# PSU.net
KiCad netlist of a schematic drawn in Altium Designer
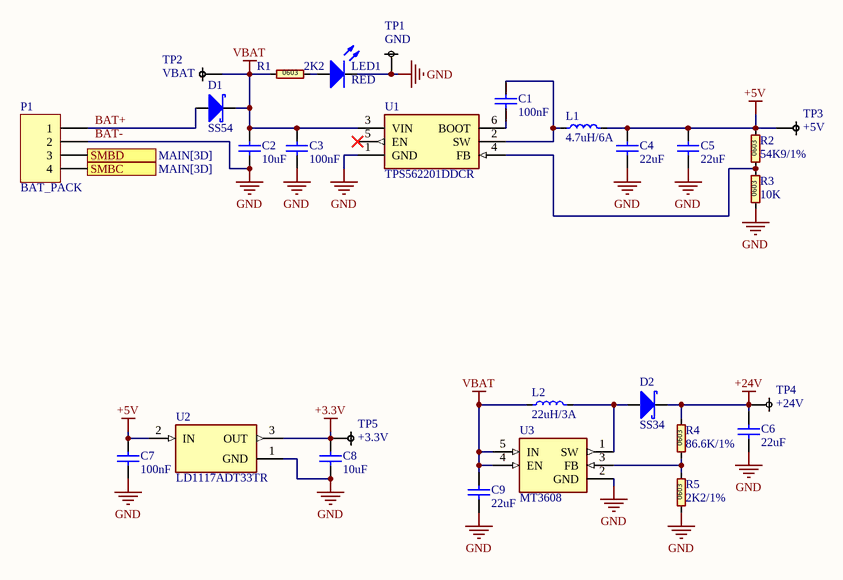
[diagram p0: PSU.SchDoc]

(export (version "E")
  (design (tool "Eeschema 10.0.6"))
  (components
    (comp (ref "C1")
      (value "100nF")
      (footprint "C0603")
      (description "0603 SMD Non-Polarity Capacitor")
      (fields (field (name "MFR.PART #") "CC1206KRX7R9BB104") (field (name "LCSC PART #") "C82601"))
      (libsource (lib "AB_SF") (part "Capacitor 0603 (Inch)"))
    )
    (comp (ref "C2")
      (value "10uF")
      (footprint "C1206")
      (description "1206 SMD Non-Polarity Capacitor")
      (fields (field (name "MFR.PART #") "CC1206KKX5R9BB106") (field (name "LCSC PART #") "C100122"))
      (libsource (lib "AB_SF") (part "Capacitor 1206 (Inch)"))
    )
    (comp (ref "C3")
      (value "100nF")
      (footprint "C0603")
      (description "0603 SMD Non-Polarity Capacitor")
      (libsource (lib "AB_SF") (part "Capacitor 0603 (Inch)"))
    )
    (comp (ref "C4")
      (value "22uF")
      (footprint "C0603")
      (description "0603 SMD Non-Polarity Capacitor")
      (fields (field (name "MFR.PART #") "GRM188R61A226ME15D") (field (name "LCSC PART #") "C84419"))
      (libsource (lib "AB_SF") (part "Capacitor 0603 (Inch)"))
    )
    (comp (ref "C5")
      (value "22uF")
      (footprint "C0603")
      (description "0603 SMD Non-Polarity Capacitor")
      (fields (field (name "MFR.PART #") "GRM188R61A226ME15D") (field (name "LCSC PART #") "C84419"))
      (libsource (lib "AB_SF") (part "Capacitor 0603 (Inch)"))
    )
    (comp (ref "C6")
      (value "22uF")
      (footprint "C1206")
      (description "1206 SMD Non-Polarity Capacitor")
      (fields (field (name "MFR.PART #") "CC1206KKX5R8BB226") (field (name "LCSC PART #") "C2178233"))
      (libsource (lib "AB_SF") (part "Capacitor 1206 (Inch)"))
    )
    (comp (ref "C7")
      (value "100nF")
      (footprint "C0603")
      (description "0603 SMD Non-Polarity Capacitor")
      (libsource (lib "AB_SF") (part "Capacitor 0603 (Inch)"))
    )
    (comp (ref "C8")
      (value "10uF")
      (footprint "C1206")
      (description "1206 SMD Non-Polarity Capacitor")
      (libsource (lib "AB_SF") (part "Capacitor 1206 (Inch)"))
    )
    (comp (ref "C9")
      (value "22uF")
      (footprint "C1206")
      (description "1206 SMD Non-Polarity Capacitor")
      (fields (field (name "MFR.PART #") "CC1206KKX5R8BB226") (field (name "LCSC PART #") "C2178233"))
      (libsource (lib "AB_SF") (part "Capacitor 1206 (Inch)"))
    )
    (comp (ref "D1")
      (value "SS54")
      (footprint "DO-214AC")
      (description "40V Independent 550mV@5A 5A SMA(DO-214AC) Schottky Diodes")
      (fields (field (name "LCSC PART #") "C22452"))
      (libsource (lib "AB_SF") (part "SS54"))
    )
    (comp (ref "D2")
      (value "SS34")
      (footprint "DO-214AC")
      (description "Schottky SS34 DO-214AC")
      (fields (field (name "LCSC PART #") "C3040628"))
      (libsource (lib "AB_SF") (part "SS34"))
    )
    (comp (ref "L1")
      (value "4.7uH/6A")
      (footprint "IND_2926 (7467)")
      (description "Inductor with Package: 2926 (7467)")
      (fields (field (name "MFR.PART #") "FXL0630-4R7-M") (field (name "LCSC PART #") "C167220"))
      (libsource (lib "AB_SF") (part "INDUCTOR 2926"))
    )
    (comp (ref "L2")
      (value "22uH/3A")
      (footprint "IND_2926 (7467)")
      (description "Inductor with Package: 2926 (7467)")
      (fields (field (name "MFR.PART #") "YSPI0630A-220M") (field (name "LCSC PART #") "C497873"))
      (libsource (lib "AB_SF") (part "INDUCTOR 2926"))
    )
    (comp (ref "LED1")
      (value "RED")
      (footprint "LED0603")
      (description "0603 LED")
      (fields (field (name "MFR.PART #") "KT-0603R") (field (name "LCSC PART #") "C2286"))
      (libsource (lib "AB_SF") (part "LED 0603"))
    )
    (comp (ref "P1")
      (value "BAT_PACK")
      (footprint "JST_XH-2.54")
      (description "CONNECTOR HEADER")
      (fields (field (name "PUBLISHER") "Altium Limited"))
      (libsource (lib "AB_SF") (part "Connector 4P"))
    )
    (comp (ref "R1")
      (value "2K2")
      (footprint "R0603")
      (description "0603 SMD Thick Resistor")
      (fields (field (name "MFR.PART #") "RC0603JR-072K2L") (field (name "LCSC PART #") "C113303"))
      (libsource (lib "") (part "Resistor 0603 (Inch)_1"))
    )
    (comp (ref "R2")
      (value "54K9/1%")
      (footprint "R0603")
      (description "0603 SMD Thick Resistor")
      (fields (field (name "MFR.PART #") "RC0603FR-0754K9L") (field (name "LCSC PART #") "C185321"))
      (libsource (lib "AB_SF") (part "Resistor 0603 (Inch)"))
    )
    (comp (ref "R3")
      (value "10K")
      (footprint "R0603")
      (description "0603 SMD Thick Resistor")
      (fields (field (name "MFR.PART #") "RC0603FR-0710KL") (field (name "LCSC PART #") "C98220"))
      (libsource (lib "AB_SF") (part "Resistor 0603 (Inch)"))
    )
    (comp (ref "R4")
      (value "86.6K/1%")
      (footprint "R0603")
      (description "0603 SMD Thick Resistor")
      (fields (field (name "MFR.PART #") "RC0603FR-0786K6L") (field (name "LCSC PART #") "C141683"))
      (libsource (lib "AB_SF") (part "Resistor 0603 (Inch)"))
    )
    (comp (ref "R5")
      (value "2K2/1%")
      (footprint "R0603")
      (description "0603 SMD Thick Resistor")
      (fields (field (name "MFR.PART #") "RC0603JR-072K2L") (field (name "LCSC PART #") "C113303"))
      (libsource (lib "AB_SF") (part "Resistor 0603 (Inch)"))
    )
    (comp (ref "TP1")
      (value "GND")
      (footprint "PAD")
      (description "Thick Pad")
      (libsource (lib "AB_SF") (part "Test Point"))
    )
    (comp (ref "TP2")
      (value "VBAT")
      (footprint "PAD")
      (description "Thick Pad")
      (libsource (lib "AB_SF") (part "Test Point"))
    )
    (comp (ref "TP3")
      (value "+5V")
      (footprint "PAD")
      (description "Thick Pad")
      (libsource (lib "AB_SF") (part "Test Point"))
    )
    (comp (ref "TP4")
      (value "+24V")
      (footprint "PAD_HOLE")
      (description "Thick Pad")
      (libsource (lib "AB_SF") (part "Test Point"))
    )
    (comp (ref "TP5")
      (value "+3.3V")
      (footprint "PAD")
      (description "Thick Pad")
      (libsource (lib "AB_SF") (part "Test Point"))
    )
    (comp (ref "U1")
      (value "TPS562201DDCR")
      (footprint "SOT-23-6")
      (description "4.5 V to 17 V input, 2 A output, synchronous step-down converter in Eco-mode")
      (fields (field (name "LCSC PART #") "C90061"))
      (libsource (lib "AB_SF") (part "TPS562201DDCR"))
    )
    (comp (ref "U2")
      (value "LD1117ADT33TR")
      (footprint "DPAK")
      (description "Linear Voltage Regulator IC Positive Fixed 1 Output 3.3V 1A")
      (fields (field (name "LCSC PART #") "C157401"))
      (libsource (lib "AB_SF") (part "LD1117ADT33TR"))
    )
    (comp (ref "U3")
      (value "MT3608")
      (footprint "SOT-23-6")
      (description "High Efficiency 1.2MHz2A Step Up Converter")
      (fields (field (name "LCSC PART #") "C84817"))
      (libsource (lib "AB_SF") (part "MT3608"))
    )
  )
  (nets
    (net (code "1") (name "+3.3V") (class "Default")
      (node (ref "C8") (pin "2") (pinfunction "2_2") (pintype "passive"))
      (node (ref "TP5") (pin "1") (pinfunction "1_1") (pintype "passive"))
      (node (ref "U2") (pin "3") (pinfunction "OUT_3") (pintype "output"))
    )
    (net (code "2") (name "+5V") (class "Default")
      (node (ref "C4") (pin "2") (pinfunction "2_2") (pintype "passive"))
      (node (ref "C5") (pin "2") (pinfunction "2_2") (pintype "passive"))
      (node (ref "C7") (pin "2") (pinfunction "2_2") (pintype "passive"))
      (node (ref "L1") (pin "2") (pinfunction "2_2") (pintype "passive"))
      (node (ref "R2") (pin "2") (pinfunction "2_2") (pintype "passive"))
      (node (ref "TP3") (pin "1") (pinfunction "1_1") (pintype "passive"))
      (node (ref "U2") (pin "2") (pinfunction "IN_2") (pintype "input"))
    )
    (net (code "3") (name "+24V") (class "Default")
      (node (ref "C6") (pin "2") (pinfunction "2_2") (pintype "passive"))
      (node (ref "D2") (pin "C") (pinfunction "K_C") (pintype "passive"))
      (node (ref "R4") (pin "2") (pinfunction "2_2") (pintype "passive"))
      (node (ref "TP4") (pin "1") (pinfunction "1_1") (pintype "passive"))
    )
    (net (code "4") (name "/BAT+") (class "Default")
      (node (ref "D1") (pin "A") (pinfunction "A_A") (pintype "passive"))
      (node (ref "P1") (pin "1") (pinfunction "1_1") (pintype "passive"))
    )
    (net (code "5") (name "/SMBC") (class "Default")
      (node (ref "P1") (pin "4") (pinfunction "4_4") (pintype "passive"))
    )
    (net (code "6") (name "/SMBD") (class "Default")
      (node (ref "P1") (pin "3") (pinfunction "3_3") (pintype "passive"))
    )
    (net (code "7") (name "GND") (class "Default")
      (node (ref "C2") (pin "1") (pinfunction "1_1") (pintype "passive"))
      (node (ref "C3") (pin "1") (pinfunction "1_1") (pintype "passive"))
      (node (ref "C4") (pin "1") (pinfunction "1_1") (pintype "passive"))
      (node (ref "C5") (pin "1") (pinfunction "1_1") (pintype "passive"))
      (node (ref "C6") (pin "1") (pinfunction "1_1") (pintype "passive"))
      (node (ref "C7") (pin "1") (pinfunction "1_1") (pintype "passive"))
      (node (ref "C8") (pin "1") (pinfunction "1_1") (pintype "passive"))
      (node (ref "C9") (pin "1") (pinfunction "1_1") (pintype "passive"))
      (node (ref "LED1") (pin "2") (pinfunction "K_2") (pintype "passive"))
      (node (ref "P1") (pin "2") (pinfunction "2_2") (pintype "passive"))
      (node (ref "R3") (pin "1") (pinfunction "1_1") (pintype "passive"))
      (node (ref "R5") (pin "1") (pinfunction "1_1") (pintype "passive"))
      (node (ref "TP1") (pin "1") (pinfunction "1_1") (pintype "passive"))
      (node (ref "U1") (pin "1") (pinfunction "GND_1") (pintype "power_in"))
      (node (ref "U2") (pin "1") (pinfunction "GND_1") (pintype "power_in"))
      (node (ref "U3") (pin "2") (pinfunction "GND_2") (pintype "power_in"))
    )
    (net (code "8") (name "Net-(LED1-A)") (class "Default")
      (node (ref "LED1") (pin "1") (pinfunction "A_1") (pintype "passive"))
      (node (ref "R1") (pin "2") (pinfunction "2_2") (pintype "passive"))
    )
    (net (code "9") (name "Net-(U1-BOOT)") (class "Default")
      (node (ref "C1") (pin "1") (pinfunction "1_1") (pintype "passive"))
      (node (ref "U1") (pin "6") (pinfunction "BOOT_6") (pintype "passive"))
    )
    (net (code "10") (name "Net-(U1-FB)") (class "Default")
      (node (ref "R2") (pin "1") (pinfunction "1_1") (pintype "passive"))
      (node (ref "R3") (pin "2") (pinfunction "2_2") (pintype "passive"))
      (node (ref "U1") (pin "4") (pinfunction "FB_4") (pintype "input"))
    )
    (net (code "11") (name "Net-(U1-SW)") (class "Default")
      (node (ref "C1") (pin "2") (pinfunction "2_2") (pintype "passive"))
      (node (ref "L1") (pin "1") (pinfunction "1_1") (pintype "passive"))
      (node (ref "U1") (pin "2") (pinfunction "SW_2") (pintype "passive"))
    )
    (net (code "12") (name "Net-(U3-FB)") (class "Default")
      (node (ref "R4") (pin "1") (pinfunction "1_1") (pintype "passive"))
      (node (ref "R5") (pin "2") (pinfunction "2_2") (pintype "passive"))
      (node (ref "U3") (pin "3") (pinfunction "FB_3") (pintype "input"))
    )
    (net (code "13") (name "Net-(U3-SW)") (class "Default")
      (node (ref "D2") (pin "A") (pinfunction "A_A") (pintype "passive"))
      (node (ref "L2") (pin "2") (pinfunction "2_2") (pintype "passive"))
      (node (ref "U3") (pin "1") (pinfunction "SW_1") (pintype "output"))
    )
    (net (code "14") (name "VBAT") (class "Default")
      (node (ref "C2") (pin "2") (pinfunction "2_2") (pintype "passive"))
      (node (ref "C3") (pin "2") (pinfunction "2_2") (pintype "passive"))
      (node (ref "C9") (pin "2") (pinfunction "2_2") (pintype "passive"))
      (node (ref "D1") (pin "C") (pinfunction "K_C") (pintype "passive"))
      (node (ref "L2") (pin "1") (pinfunction "1_1") (pintype "passive"))
      (node (ref "R1") (pin "1") (pinfunction "1_1") (pintype "passive"))
      (node (ref "TP2") (pin "1") (pinfunction "1_1") (pintype "passive"))
      (node (ref "U1") (pin "3") (pinfunction "VIN_3") (pintype "power_in"))
      (node (ref "U3") (pin "4") (pinfunction "EN_4") (pintype "input"))
      (node (ref "U3") (pin "5") (pinfunction "IN_5") (pintype "input"))
    )
    (net (code "15") (name "unconnected-(U1-EN-Pad5)") (class "Default")
      (node (ref "U1") (pin "5") (pinfunction "EN_5") (pintype "output+no_connect"))
    )
  )
)
